# polarshield_v1_4a.net
KiCad netlist of a schematic drawn in EAGLE
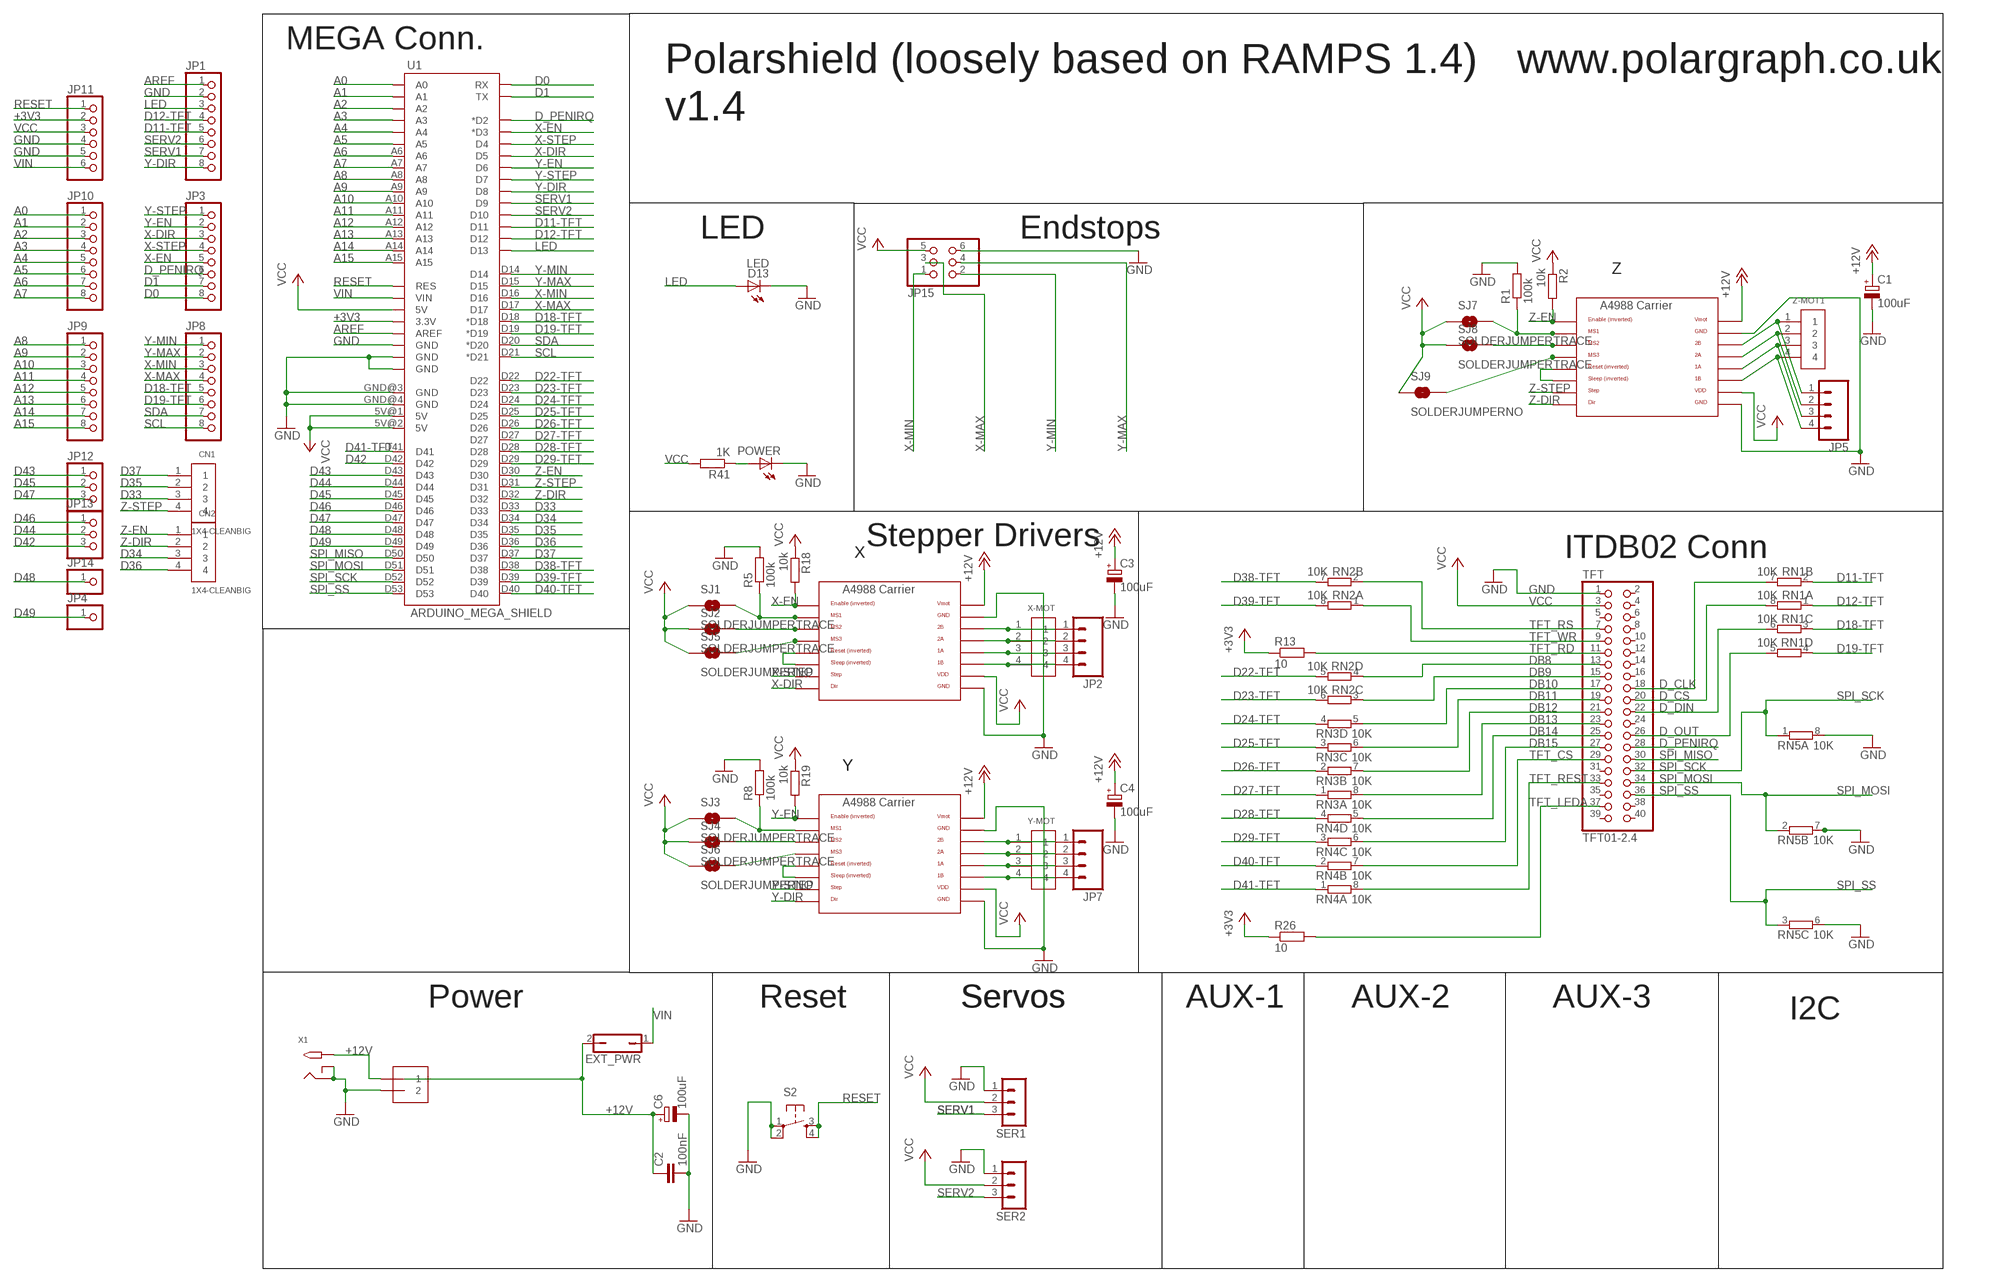
[diagram p0: schematic, sheet 1]

(export (version "E")
  (design (tool "Eeschema 10.0.6"))
  (components
    (comp (ref "C1")
      (value "100uF")
      (footprint "eagle-import:153CLV-0605")
      (libsource (lib "eagle-import") (part "CPOL-EU153CLV-0605"))
    )
    (comp (ref "C2")
      (value "100nF")
      (footprint "eagle-import:C0805")
      (libsource (lib "eagle-import") (part "C-EUC0805"))
    )
    (comp (ref "C3")
      (value "100uF")
      (footprint "eagle-import:153CLV-0605")
      (libsource (lib "eagle-import") (part "CPOL-EU153CLV-0605"))
    )
    (comp (ref "C4")
      (value "100uF")
      (footprint "eagle-import:153CLV-0605")
      (libsource (lib "eagle-import") (part "CPOL-EU153CLV-0605"))
    )
    (comp (ref "C6")
      (value "100uF")
      (footprint "eagle-import:153CLV-0605")
      (libsource (lib "eagle-import") (part "CPOL-EU153CLV-0605"))
    )
    (comp (ref "CN1")
      (value "1X4-CLEANBIG")
      (footprint "eagle-import:1X04-CLEANBIG")
      (libsource (lib "eagle-import") (part "1X4-CLEANBIG"))
    )
    (comp (ref "CN2")
      (value "1X4-CLEANBIG")
      (footprint "eagle-import:1X04-CLEANBIG")
      (libsource (lib "eagle-import") (part "1X4-CLEANBIG"))
    )
    (comp (ref "D13")
      (value "LED")
      (footprint "eagle-import:CHIP-LED0805")
      (libsource (lib "eagle-import") (part "LEDCHIP-LED0805"))
    )
    (comp (ref "EXT_PWR")
      (value "JP1Q")
      (footprint "eagle-import:JP1")
      (libsource (lib "eagle-import") (part "JP1Q"))
    )
    (comp (ref "J1")
      (value "1X2-3.5MM")
      (footprint "eagle-import:1X2-3.5MM")
      (libsource (lib "eagle-import") (part "1X2-3.5MM"))
    )
    (comp (ref "JP1")
      (value "PINHD-1X8CLEANBIG")
      (footprint "eagle-import:1X08-CLEANBIG")
      (libsource (lib "eagle-import") (part "PINHD-1X8CLEANBIG"))
    )
    (comp (ref "JP2")
      (value "M04SCREW")
      (footprint "eagle-import:SCREWTERMINAL-3.5MM-4")
      (libsource (lib "eagle-import") (part "M04SCREW"))
    )
    (comp (ref "JP3")
      (value "PINHD-1X8CLEANBIG")
      (footprint "eagle-import:1X08-CLEANBIG")
      (libsource (lib "eagle-import") (part "PINHD-1X8CLEANBIG"))
    )
    (comp (ref "JP4")
      (value "PINHD-1X1CB")
      (footprint "eagle-import:1X01-CLEANBIG")
      (libsource (lib "eagle-import") (part "PINHD-1X1CB"))
    )
    (comp (ref "JP5")
      (value "M04SCREW")
      (footprint "eagle-import:SCREWTERMINAL-3.5MM-4")
      (libsource (lib "eagle-import") (part "M04SCREW"))
    )
    (comp (ref "JP7")
      (value "M04SCREW")
      (footprint "eagle-import:SCREWTERMINAL-3.5MM-4")
      (libsource (lib "eagle-import") (part "M04SCREW"))
    )
    (comp (ref "JP8")
      (value "PINHD-1X8CLEANBIG")
      (footprint "eagle-import:1X08-CLEANBIG")
      (libsource (lib "eagle-import") (part "PINHD-1X8CLEANBIG"))
    )
    (comp (ref "JP9")
      (value "PINHD-1X8CLEANBIG")
      (footprint "eagle-import:1X08-CLEANBIG")
      (libsource (lib "eagle-import") (part "PINHD-1X8CLEANBIG"))
    )
    (comp (ref "JP10")
      (value "PINHD-1X8CLEANBIG")
      (footprint "eagle-import:1X08-CLEANBIG")
      (libsource (lib "eagle-import") (part "PINHD-1X8CLEANBIG"))
    )
    (comp (ref "JP11")
      (value "PINHD-1X6CB")
      (footprint "eagle-import:1X06-CLEANBIG")
      (libsource (lib "eagle-import") (part "PINHD-1X6CB"))
    )
    (comp (ref "JP12")
      (value "PINHD-1X3CB")
      (footprint "eagle-import:1X03-CLEANBIG")
      (libsource (lib "eagle-import") (part "PINHD-1X3CB"))
    )
    (comp (ref "JP13")
      (value "PINHD-1X3CB")
      (footprint "eagle-import:1X03-CLEANBIG")
      (libsource (lib "eagle-import") (part "PINHD-1X3CB"))
    )
    (comp (ref "JP14")
      (value "PINHD-1X1CB")
      (footprint "eagle-import:1X01-CLEANBIG")
      (libsource (lib "eagle-import") (part "PINHD-1X1CB"))
    )
    (comp (ref "JP15")
      (value "PINHD-2X3")
      (footprint "eagle-import:2X03")
      (libsource (lib "eagle-import") (part "PINHD-2X3"))
    )
    (comp (ref "POWER")
      (value "LEDCHIP-LED0805")
      (footprint "eagle-import:CHIP-LED0805")
      (libsource (lib "eagle-import") (part "LEDCHIP-LED0805"))
    )
    (comp (ref "R1")
      (value "100k")
      (footprint "eagle-import:R0805")
      (libsource (lib "eagle-import") (part "R-EU_R0805"))
    )
    (comp (ref "R2")
      (value "10k")
      (footprint "eagle-import:R0805")
      (libsource (lib "eagle-import") (part "R-EU_R0805"))
    )
    (comp (ref "R5")
      (value "100k")
      (footprint "eagle-import:R0805")
      (libsource (lib "eagle-import") (part "R-EU_R0805"))
    )
    (comp (ref "R8")
      (value "100k")
      (footprint "eagle-import:R0805")
      (libsource (lib "eagle-import") (part "R-EU_R0805"))
    )
    (comp (ref "R13")
      (value "10")
      (footprint "eagle-import:R0805")
      (libsource (lib "eagle-import") (part "resistor_R-EU_R0805"))
    )
    (comp (ref "R18")
      (value "10k")
      (footprint "eagle-import:R0805")
      (libsource (lib "eagle-import") (part "R-EU_R0805"))
    )
    (comp (ref "R19")
      (value "10k")
      (footprint "eagle-import:R0805")
      (libsource (lib "eagle-import") (part "R-EU_R0805"))
    )
    (comp (ref "R26")
      (value "10")
      (footprint "eagle-import:R0805")
      (libsource (lib "eagle-import") (part "resistor_R-EU_R0805"))
    )
    (comp (ref "R41")
      (value "1K")
      (footprint "eagle-import:R0805")
      (libsource (lib "eagle-import") (part "R-EU_R0805"))
    )
    (comp (ref "RN1")
      (value "10K")
      (footprint "eagle-import:EXBS8V")
      (libsource (lib "eagle-import") (part "4R-NEXBS8V"))
    )
    (comp (ref "RN2")
      (value "10K")
      (footprint "eagle-import:EXBS8V")
      (libsource (lib "eagle-import") (part "4R-NEXBS8V"))
    )
    (comp (ref "RN3")
      (value "10K")
      (footprint "eagle-import:EXBS8V")
      (libsource (lib "eagle-import") (part "4R-NEXBS8V"))
    )
    (comp (ref "RN4")
      (value "10K")
      (footprint "eagle-import:EXBS8V")
      (libsource (lib "eagle-import") (part "4R-NEXBS8V"))
    )
    (comp (ref "RN5")
      (value "10K")
      (footprint "eagle-import:EXBS8V")
      (libsource (lib "eagle-import") (part "4R-NEXBS8V"))
    )
    (comp (ref "S2")
      (value "TAC_SWITCHPTH")
      (footprint "eagle-import:TACTILE-PTH")
      (libsource (lib "eagle-import") (part "TAC_SWITCHPTH"))
    )
    (comp (ref "SER1")
      (value "3PIN-HEADER")
      (footprint "eagle-import:3PIN-HEADER")
      (libsource (lib "eagle-import") (part "3PIN-HEADER"))
    )
    (comp (ref "SER2")
      (value "3PIN-HEADER")
      (footprint "eagle-import:3PIN-HEADER")
      (libsource (lib "eagle-import") (part "3PIN-HEADER"))
    )
    (comp (ref "SJ1")
      (value "SOLDERJUMPERTRACE")
      (footprint "eagle-import:SJ_2S-TRACE")
      (libsource (lib "eagle-import") (part "SOLDERJUMPERTRACE"))
    )
    (comp (ref "SJ2")
      (value "SOLDERJUMPERTRACE")
      (footprint "eagle-import:SJ_2S-TRACE")
      (libsource (lib "eagle-import") (part "SOLDERJUMPERTRACE"))
    )
    (comp (ref "SJ3")
      (value "SOLDERJUMPERTRACE")
      (footprint "eagle-import:SJ_2S-TRACE")
      (libsource (lib "eagle-import") (part "SOLDERJUMPERTRACE"))
    )
    (comp (ref "SJ4")
      (value "SOLDERJUMPERTRACE")
      (footprint "eagle-import:SJ_2S-TRACE")
      (libsource (lib "eagle-import") (part "SOLDERJUMPERTRACE"))
    )
    (comp (ref "SJ5")
      (value "SOLDERJUMPERNO")
      (footprint "eagle-import:SJ_2S-NO")
      (libsource (lib "eagle-import") (part "SOLDERJUMPERNO"))
    )
    (comp (ref "SJ6")
      (value "SOLDERJUMPERNO")
      (footprint "eagle-import:SJ_2S-NO")
      (libsource (lib "eagle-import") (part "SOLDERJUMPERNO"))
    )
    (comp (ref "SJ7")
      (value "SOLDERJUMPERTRACE")
      (footprint "eagle-import:SJ_2S-TRACE")
      (libsource (lib "eagle-import") (part "SOLDERJUMPERTRACE"))
    )
    (comp (ref "SJ8")
      (value "SOLDERJUMPERTRACE")
      (footprint "eagle-import:SJ_2S-TRACE")
      (libsource (lib "eagle-import") (part "SOLDERJUMPERTRACE"))
    )
    (comp (ref "SJ9")
      (value "SOLDERJUMPERNO")
      (footprint "eagle-import:SJ_2S-NO")
      (libsource (lib "eagle-import") (part "SOLDERJUMPERNO"))
    )
    (comp (ref "TFT")
      (value "TFT01-2.4")
      (footprint "eagle-import:TFT01-2.4")
      (libsource (lib "eagle-import") (part "TFT01-2.4"))
    )
    (comp (ref "U$1")
      (value "A4988BREAKOUT")
      (footprint "eagle-import:A4988BREAKOUT")
      (libsource (lib "eagle-import") (part "A4988BREAKOUT"))
    )
    (comp (ref "U$6")
      (value "A4988BREAKOUT")
      (footprint "eagle-import:A4988BREAKOUT")
      (libsource (lib "eagle-import") (part "A4988BREAKOUT"))
    )
    (comp (ref "U$7")
      (value "A4988BREAKOUT")
      (footprint "eagle-import:A4988BREAKOUT")
      (libsource (lib "eagle-import") (part "A4988BREAKOUT"))
    )
    (comp (ref "U1")
      (value "ARDUINO_MEGA_SHIELD")
      (footprint "eagle-import:ARDUINO_MEGA_SHIELD")
      (libsource (lib "eagle-import") (part "ARDUINO_MEGA_SHIELD"))
    )
    (comp (ref "X-MOT")
      (value "1X4-BIG")
      (footprint "eagle-import:1X04-BIG")
      (libsource (lib "eagle-import") (part "1X4-BIG"))
    )
    (comp (ref "X1")
      (value "2.1MMJACKTHM")
      (footprint "eagle-import:PJ-102A")
      (libsource (lib "eagle-import") (part "2.1MMJACKTHM"))
    )
    (comp (ref "Y-MOT")
      (value "1X4-BIG")
      (footprint "eagle-import:1X04-BIG")
      (libsource (lib "eagle-import") (part "1X4-BIG"))
    )
    (comp (ref "Z-MOT1")
      (value "1X4-BIG")
      (footprint "eagle-import:1X04-BIG")
      (libsource (lib "eagle-import") (part "1X4-BIG"))
    )
  )
  (nets
    (net (code "1") (name "+3V3") (class "Default")
      (node (ref "JP11") (pin "2") (pinfunction "2_2") (pintype "passive"))
      (node (ref "R13") (pin "1") (pinfunction "1_1") (pintype "passive"))
      (node (ref "R26") (pin "1") (pinfunction "1_1") (pintype "passive"))
      (node (ref "U1") (pin "3.3V") (pinfunction "3.3V_3.3V") (pintype "bidirectional"))
    )
    (net (code "2") (name "+12V") (class "Default")
      (node (ref "C1") (pin "+") (pinfunction "+_+") (pintype "passive"))
      (node (ref "C2") (pin "1") (pinfunction "1_1") (pintype "passive"))
      (node (ref "C3") (pin "+") (pinfunction "+_+") (pintype "passive"))
      (node (ref "C4") (pin "+") (pinfunction "+_+") (pintype "passive"))
      (node (ref "C6") (pin "+") (pinfunction "+_+") (pintype "passive"))
      (node (ref "EXT_PWR") (pin "2") (pinfunction "2_2") (pintype "passive"))
      (node (ref "J1") (pin "1") (pinfunction "1_1") (pintype "passive"))
      (node (ref "U$1") (pin "VMOT") (pinfunction "VMOT_VMOT") (pintype "power_in"))
      (node (ref "U$6") (pin "VMOT") (pinfunction "VMOT_VMOT") (pintype "power_in"))
      (node (ref "U$7") (pin "VMOT") (pinfunction "VMOT_VMOT") (pintype "power_in"))
      (node (ref "X1") (pin "TIP") (pinfunction "TIP_TIP") (pintype "bidirectional"))
    )
    (net (code "3") (name "/A0") (class "Default")
      (node (ref "JP10") (pin "1") (pinfunction "1_1") (pintype "passive"))
      (node (ref "U1") (pin "A0") (pinfunction "A0_A0") (pintype "bidirectional"))
    )
    (net (code "4") (name "/A1") (class "Default")
      (node (ref "JP10") (pin "2") (pinfunction "2_2") (pintype "passive"))
      (node (ref "U1") (pin "A1") (pinfunction "A1_A1") (pintype "bidirectional"))
    )
    (net (code "5") (name "/A2") (class "Default")
      (node (ref "JP10") (pin "3") (pinfunction "3_3") (pintype "passive"))
      (node (ref "U1") (pin "A2") (pinfunction "A2_A2") (pintype "bidirectional"))
    )
    (net (code "6") (name "/A3") (class "Default")
      (node (ref "JP10") (pin "4") (pinfunction "4_4") (pintype "passive"))
      (node (ref "U1") (pin "A3") (pinfunction "A3_A3") (pintype "bidirectional"))
    )
    (net (code "7") (name "/A4") (class "Default")
      (node (ref "JP10") (pin "5") (pinfunction "5_5") (pintype "passive"))
      (node (ref "U1") (pin "A4") (pinfunction "A4_A4") (pintype "bidirectional"))
    )
    (net (code "8") (name "/A5") (class "Default")
      (node (ref "JP10") (pin "6") (pinfunction "6_6") (pintype "passive"))
      (node (ref "U1") (pin "A5") (pinfunction "A5_A5") (pintype "bidirectional"))
    )
    (net (code "9") (name "/A6") (class "Default")
      (node (ref "JP10") (pin "7") (pinfunction "7_7") (pintype "passive"))
      (node (ref "U1") (pin "A6") (pinfunction "A6_A6") (pintype "bidirectional"))
    )
    (net (code "10") (name "/A7") (class "Default")
      (node (ref "JP10") (pin "8") (pinfunction "8_8") (pintype "passive"))
      (node (ref "U1") (pin "A7") (pinfunction "A7_A7") (pintype "bidirectional"))
    )
    (net (code "11") (name "/A8") (class "Default")
      (node (ref "JP9") (pin "1") (pinfunction "1_1") (pintype "passive"))
      (node (ref "U1") (pin "A8") (pinfunction "A8_A8") (pintype "bidirectional"))
    )
    (net (code "12") (name "/A9") (class "Default")
      (node (ref "JP9") (pin "2") (pinfunction "2_2") (pintype "passive"))
      (node (ref "U1") (pin "A9") (pinfunction "A9_A9") (pintype "bidirectional"))
    )
    (net (code "13") (name "/A10") (class "Default")
      (node (ref "JP9") (pin "3") (pinfunction "3_3") (pintype "passive"))
      (node (ref "U1") (pin "A10") (pinfunction "A10_A10") (pintype "bidirectional"))
    )
    (net (code "14") (name "/A11") (class "Default")
      (node (ref "JP9") (pin "4") (pinfunction "4_4") (pintype "passive"))
      (node (ref "U1") (pin "A11") (pinfunction "A11_A11") (pintype "bidirectional"))
    )
    (net (code "15") (name "/A12") (class "Default")
      (node (ref "JP9") (pin "5") (pinfunction "5_5") (pintype "passive"))
      (node (ref "U1") (pin "A12") (pinfunction "A12_A12") (pintype "bidirectional"))
    )
    (net (code "16") (name "/A13") (class "Default")
      (node (ref "JP9") (pin "6") (pinfunction "6_6") (pintype "passive"))
      (node (ref "U1") (pin "A13") (pinfunction "A13_A13") (pintype "bidirectional"))
    )
    (net (code "17") (name "/A14") (class "Default")
      (node (ref "JP9") (pin "7") (pinfunction "7_7") (pintype "passive"))
      (node (ref "U1") (pin "A14") (pinfunction "A14_A14") (pintype "bidirectional"))
    )
    (net (code "18") (name "/A15") (class "Default")
      (node (ref "JP9") (pin "8") (pinfunction "8_8") (pintype "passive"))
      (node (ref "U1") (pin "A15") (pinfunction "A15_A15") (pintype "bidirectional"))
    )
    (net (code "19") (name "/AREF") (class "Default")
      (node (ref "JP1") (pin "1") (pinfunction "1_1") (pintype "passive"))
      (node (ref "U1") (pin "AREF") (pinfunction "AREF_AREF") (pintype "bidirectional"))
    )
    (net (code "20") (name "/D0") (class "Default")
      (node (ref "JP3") (pin "8") (pinfunction "8_8") (pintype "passive"))
      (node (ref "U1") (pin "RX") (pinfunction "RX_RX") (pintype "bidirectional"))
    )
    (net (code "21") (name "/D1") (class "Default")
      (node (ref "JP3") (pin "7") (pinfunction "7_7") (pintype "passive"))
      (node (ref "U1") (pin "TX") (pinfunction "TX_TX") (pintype "bidirectional"))
    )
    (net (code "22") (name "/D11-TFT") (class "Default")
      (node (ref "JP1") (pin "5") (pinfunction "5_5") (pintype "passive"))
      (node (ref "RN1") (pin "2") (pinfunction "1_2") (pintype "passive"))
      (node (ref "U1") (pin "D11") (pinfunction "D11_D11") (pintype "bidirectional"))
    )
    (net (code "23") (name "/D12-TFT") (class "Default")
      (node (ref "JP1") (pin "4") (pinfunction "4_4") (pintype "passive"))
      (node (ref "RN1") (pin "1") (pinfunction "1_1") (pintype "passive"))
      (node (ref "U1") (pin "D12") (pinfunction "D12_D12") (pintype "bidirectional"))
    )
    (net (code "24") (name "/D18-TFT") (class "Default")
      (node (ref "JP8") (pin "5") (pinfunction "5_5") (pintype "passive"))
      (node (ref "RN1") (pin "3") (pinfunction "1_3") (pintype "passive"))
      (node (ref "U1") (pin "D18") (pinfunction "*D18_D18") (pintype "bidirectional"))
    )
    (net (code "25") (name "/D19-TFT") (class "Default")
      (node (ref "JP8") (pin "6") (pinfunction "6_6") (pintype "passive"))
      (node (ref "RN1") (pin "4") (pinfunction "1_4") (pintype "passive"))
      (node (ref "U1") (pin "D19") (pinfunction "*D19_D19") (pintype "bidirectional"))
    )
    (net (code "26") (name "/D22-TFT") (class "Default")
      (node (ref "RN2") (pin "5") (pinfunction "2_5") (pintype "passive"))
      (node (ref "U1") (pin "D22") (pinfunction "D22_D22") (pintype "bidirectional"))
    )
    (net (code "27") (name "/D23-TFT") (class "Default")
      (node (ref "RN2") (pin "6") (pinfunction "2_6") (pintype "passive"))
      (node (ref "U1") (pin "D23") (pinfunction "D23_D23") (pintype "bidirectional"))
    )
    (net (code "28") (name "/D24-TFT") (class "Default")
      (node (ref "RN3") (pin "4") (pinfunction "1_4") (pintype "passive"))
      (node (ref "U1") (pin "D24") (pinfunction "D24_D24") (pintype "bidirectional"))
    )
    (net (code "29") (name "/D25-TFT") (class "Default")
      (node (ref "RN3") (pin "3") (pinfunction "1_3") (pintype "passive"))
      (node (ref "U1") (pin "D25") (pinfunction "D25_D25") (pintype "bidirectional"))
    )
    (net (code "30") (name "/D26-TFT") (class "Default")
      (node (ref "RN3") (pin "2") (pinfunction "1_2") (pintype "passive"))
      (node (ref "U1") (pin "D26") (pinfunction "D26_D26") (pintype "bidirectional"))
    )
    (net (code "31") (name "/D27-TFT") (class "Default")
      (node (ref "RN3") (pin "1") (pinfunction "1_1") (pintype "passive"))
      (node (ref "U1") (pin "D27") (pinfunction "D27_D27") (pintype "bidirectional"))
    )
    (net (code "32") (name "/D28-TFT") (class "Default")
      (node (ref "RN4") (pin "4") (pinfunction "1_4") (pintype "passive"))
      (node (ref "U1") (pin "D28") (pinfunction "D28_D28") (pintype "bidirectional"))
    )
    (net (code "33") (name "/D29-TFT") (class "Default")
      (node (ref "RN4") (pin "3") (pinfunction "1_3") (pintype "passive"))
      (node (ref "U1") (pin "D29") (pinfunction "D29_D29") (pintype "bidirectional"))
    )
    (net (code "34") (name "/D33") (class "Default")
      (node (ref "CN1") (pin "3") (pinfunction "3_3") (pintype "bidirectional"))
      (node (ref "U1") (pin "D33") (pinfunction "D33_D33") (pintype "bidirectional"))
    )
    (net (code "35") (name "/D34") (class "Default")
      (node (ref "CN2") (pin "3") (pinfunction "3_3") (pintype "bidirectional"))
      (node (ref "U1") (pin "D34") (pinfunction "D34_D34") (pintype "bidirectional"))
    )
    (net (code "36") (name "/D35") (class "Default")
      (node (ref "CN1") (pin "2") (pinfunction "2_2") (pintype "bidirectional"))
      (node (ref "U1") (pin "D35") (pinfunction "D35_D35") (pintype "bidirectional"))
    )
    (net (code "37") (name "/D36") (class "Default")
      (node (ref "CN2") (pin "4") (pinfunction "4_4") (pintype "bidirectional"))
      (node (ref "U1") (pin "D36") (pinfunction "D36_D36") (pintype "bidirectional"))
    )
    (net (code "38") (name "/D37") (class "Default")
      (node (ref "CN1") (pin "1") (pinfunction "1_1") (pintype "bidirectional"))
      (node (ref "U1") (pin "D37") (pinfunction "D37_D37") (pintype "bidirectional"))
    )
    (net (code "39") (name "/D38-TFT") (class "Default")
      (node (ref "RN2") (pin "7") (pinfunction "2_7") (pintype "passive"))
      (node (ref "U1") (pin "D38") (pinfunction "D38_D38") (pintype "bidirectional"))
    )
    (net (code "40") (name "/D39-TFT") (class "Default")
      (node (ref "RN2") (pin "8") (pinfunction "2_8") (pintype "passive"))
      (node (ref "U1") (pin "D39") (pinfunction "D39_D39") (pintype "bidirectional"))
    )
    (net (code "41") (name "/D40-TFT") (class "Default")
      (node (ref "RN4") (pin "2") (pinfunction "1_2") (pintype "passive"))
      (node (ref "U1") (pin "D40") (pinfunction "D40_D40") (pintype "bidirectional"))
    )
    (net (code "42") (name "/D41-TFT") (class "Default")
      (node (ref "RN4") (pin "1") (pinfunction "1_1") (pintype "passive"))
      (node (ref "U1") (pin "D41") (pinfunction "D41_D41") (pintype "bidirectional"))
    )
    (net (code "43") (name "/D42") (class "Default")
      (node (ref "JP13") (pin "3") (pinfunction "3_3") (pintype "passive"))
      (node (ref "U1") (pin "D42") (pinfunction "D42_D42") (pintype "bidirectional"))
    )
    (net (code "44") (name "/D43") (class "Default")
      (node (ref "JP12") (pin "1") (pinfunction "1_1") (pintype "passive"))
      (node (ref "U1") (pin "D43") (pinfunction "D43_D43") (pintype "bidirectional"))
    )
    (net (code "45") (name "/D44") (class "Default")
      (node (ref "JP13") (pin "2") (pinfunction "2_2") (pintype "passive"))
      (node (ref "U1") (pin "D44") (pinfunction "D44_D44") (pintype "bidirectional"))
    )
    (net (code "46") (name "/D45") (class "Default")
      (node (ref "JP12") (pin "2") (pinfunction "2_2") (pintype "passive"))
      (node (ref "U1") (pin "D45") (pinfunction "D45_D45") (pintype "bidirectional"))
    )
    (net (code "47") (name "/D46") (class "Default")
      (node (ref "JP13") (pin "1") (pinfunction "1_1") (pintype "passive"))
      (node (ref "U1") (pin "D46") (pinfunction "D46_D46") (pintype "bidirectional"))
    )
    (net (code "48") (name "/D47") (class "Default")
      (node (ref "JP12") (pin "3") (pinfunction "3_3") (pintype "passive"))
      (node (ref "U1") (pin "D47") (pinfunction "D47_D47") (pintype "bidirectional"))
    )
    (net (code "49") (name "/D48") (class "Default")
      (node (ref "JP14") (pin "1") (pinfunction "1_1") (pintype "passive"))
      (node (ref "U1") (pin "D48") (pinfunction "D48_D48") (pintype "bidirectional"))
    )
    (net (code "50") (name "/D49") (class "Default")
      (node (ref "JP4") (pin "1") (pinfunction "1_1") (pintype "passive"))
      (node (ref "U1") (pin "D49") (pinfunction "D49_D49") (pintype "bidirectional"))
    )
    (net (code "51") (name "/DB8") (class "Default")
      (node (ref "RN2") (pin "4") (pinfunction "1_4") (pintype "passive"))
      (node (ref "TFT") (pin "13") (pinfunction "13_13") (pintype "passive"))
    )
    (net (code "52") (name "/DB9") (class "Default")
      (node (ref "RN2") (pin "3") (pinfunction "1_3") (pintype "passive"))
      (node (ref "TFT") (pin "15") (pinfunction "15_15") (pintype "passive"))
    )
    (net (code "53") (name "/DB10") (class "Default")
      (node (ref "RN3") (pin "5") (pinfunction "2_5") (pintype "passive"))
      (node (ref "TFT") (pin "17") (pinfunction "17_17") (pintype "passive"))
    )
    (net (code "54") (name "/DB11") (class "Default")
      (node (ref "RN3") (pin "6") (pinfunction "2_6") (pintype "passive"))
      (node (ref "TFT") (pin "19") (pinfunction "19_19") (pintype "passive"))
    )
    (net (code "55") (name "/DB12") (class "Default")
      (node (ref "RN3") (pin "7") (pinfunction "2_7") (pintype "passive"))
      (node (ref "TFT") (pin "21") (pinfunction "21_21") (pintype "passive"))
    )
    (net (code "56") (name "/DB13") (class "Default")
      (node (ref "RN3") (pin "8") (pinfunction "2_8") (pintype "passive"))
      (node (ref "TFT") (pin "23") (pinfunction "23_23") (pintype "passive"))
    )
    (net (code "57") (name "/DB14") (class "Default")
      (node (ref "RN4") (pin "5") (pinfunction "2_5") (pintype "passive"))
      (node (ref "TFT") (pin "25") (pinfunction "25_25") (pintype "passive"))
    )
    (net (code "58") (name "/DB15") (class "Default")
      (node (ref "RN4") (pin "6") (pinfunction "2_6") (pintype "passive"))
      (node (ref "TFT") (pin "27") (pinfunction "27_27") (pintype "passive"))
    )
    (net (code "59") (name "/D_CLK") (class "Default")
      (node (ref "RN1") (pin "7") (pinfunction "2_7") (pintype "passive"))
      (node (ref "TFT") (pin "18") (pinfunction "18_18") (pintype "passive"))
    )
    (net (code "60") (name "/D_CS") (class "Default")
      (node (ref "RN1") (pin "8") (pinfunction "2_8") (pintype "passive"))
      (node (ref "TFT") (pin "20") (pinfunction "20_20") (pintype "passive"))
    )
    (net (code "61") (name "/D_DIN") (class "Default")
      (node (ref "RN1") (pin "6") (pinfunction "2_6") (pintype "passive"))
      (node (ref "TFT") (pin "22") (pinfunction "22_22") (pintype "passive"))
    )
    (net (code "62") (name "/D_OUT") (class "Default")
      (node (ref "RN1") (pin "5") (pinfunction "2_5") (pintype "passive"))
      (node (ref "TFT") (pin "26") (pinfunction "26_26") (pintype "passive"))
    )
    (net (code "63") (name "/D_PENIRQ") (class "Default")
      (node (ref "JP3") (pin "6") (pinfunction "6_6") (pintype "passive"))
      (node (ref "TFT") (pin "28") (pinfunction "28_28") (pintype "passive"))
      (node (ref "U1") (pin "D2") (pinfunction "*D2_D2") (pintype "bidirectional"))
    )
    (net (code "64") (name "/LED") (class "Default")
      (node (ref "D13") (pin "A") (pinfunction "A_A") (pintype "passive"))
      (node (ref "JP1") (pin "3") (pinfunction "3_3") (pintype "passive"))
      (node (ref "U1") (pin "D13") (pinfunction "D13_D13") (pintype "bidirectional"))
    )
    (net (code "65") (name "/RESET") (class "Default")
      (node (ref "JP11") (pin "1") (pinfunction "1_1") (pintype "passive"))
      (node (ref "S2") (pin "3") (pinfunction "3_3") (pintype "passive"))
      (node (ref "S2") (pin "4") (pinfunction "4_4") (pintype "passive"))
      (node (ref "U1") (pin "RES") (pinfunction "RES_RES") (pintype "bidirectional"))
    )
    (net (code "66") (name "/SCL") (class "Default")
      (node (ref "JP8") (pin "8") (pinfunction "8_8") (pintype "passive"))
      (node (ref "U1") (pin "D21") (pinfunction "*D21_D21") (pintype "bidirectional"))
    )
    (net (code "67") (name "/SDA") (class "Default")
      (node (ref "JP8") (pin "7") (pinfunction "7_7") (pintype "passive"))
      (node (ref "U1") (pin "D20") (pinfunction "*D20_D20") (pintype "bidirectional"))
    )
    (net (code "68") (name "/SERV1") (class "Default")
      (node (ref "JP1") (pin "7") (pinfunction "7_7") (pintype "passive"))
      (node (ref "SER1") (pin "3") (pinfunction "3_3") (pintype "passive"))
      (node (ref "U1") (pin "D9") (pinfunction "D9_D9") (pintype "bidirectional"))
    )
    (net (code "69") (name "/SERV2") (class "Default")
      (node (ref "JP1") (pin "6") (pinfunction "6_6") (pintype "passive"))
      (node (ref "SER2") (pin "3") (pinfunction "3_3") (pintype "passive"))
      (node (ref "U1") (pin "D10") (pinfunction "D10_D10") (pintype "bidirectional"))
    )
    (net (code "70") (name "/SPI_MISO") (class "Default")
      (node (ref "TFT") (pin "30") (pinfunction "30_30") (pintype "passive"))
      (node (ref "U1") (pin "D50") (pinfunction "D50_D50") (pintype "bidirectional"))
    )
    (net (code "71") (name "/SPI_MOSI") (class "Default")
      (node (ref "RN5") (pin "2") (pinfunction "1_2") (pintype "passive"))
      (node (ref "TFT") (pin "34") (pinfunction "34_34") (pintype "passive"))
      (node (ref "U1") (pin "D51") (pinfunction "D51_D51") (pintype "bidirectional"))
    )
    (net (code "72") (name "/SPI_SCK") (class "Default")
      (node (ref "RN5") (pin "1") (pinfunction "1_1") (pintype "passive"))
      (node (ref "TFT") (pin "32") (pinfunction "32_32") (pintype "passive"))
      (node (ref "U1") (pin "D52") (pinfunction "D52_D52") (pintype "bidirectional"))
    )
    (net (code "73") (name "/SPI_SS") (class "Default")
      (node (ref "RN5") (pin "3") (pinfunction "1_3") (pintype "passive"))
      (node (ref "TFT") (pin "36") (pinfunction "36_36") (pintype "passive"))
      (node (ref "U1") (pin "D53") (pinfunction "D53_D53") (pintype "bidirectional"))
    )
    (net (code "74") (name "/TFT_CS") (class "Default")
      (node (ref "RN4") (pin "7") (pinfunction "2_7") (pintype "passive"))
      (node (ref "TFT") (pin "29") (pinfunction "29_29") (pintype "passive"))
    )
    (net (code "75") (name "/TFT_LEDA") (class "Default")
      (node (ref "R26") (pin "2") (pinfunction "2_2") (pintype "passive"))
      (node (ref "TFT") (pin "37") (pinfunction "37_37") (pintype "passive"))
    )
    (net (code "76") (name "/TFT_RD") (class "Default")
      (node (ref "R13") (pin "2") (pinfunction "2_2") (pintype "passive"))
      (node (ref "TFT") (pin "11") (pinfunction "11_11") (pintype "passive"))
    )
    (net (code "77") (name "/TFT_REST") (class "Default")
      (node (ref "RN4") (pin "8") (pinfunction "2_8") (pintype "passive"))
      (node (ref "TFT") (pin "33") (pinfunction "33_33") (pintype "passive"))
    )
    (net (code "78") (name "/TFT_RS") (class "Default")
      (node (ref "RN2") (pin "2") (pinfunction "1_2") (pintype "passive"))
      (node (ref "TFT") (pin "7") (pinfunction "7_7") (pintype "passive"))
    )
    (net (code "79") (name "/TFT_WR") (class "Default")
      (node (ref "RN2") (pin "1") (pinfunction "1_1") (pintype "passive"))
      (node (ref "TFT") (pin "9") (pinfunction "9_9") (pintype "passive"))
    )
    (net (code "80") (name "/VIN") (class "Default")
      (node (ref "EXT_PWR") (pin "1") (pinfunction "1_1") (pintype "passive"))
      (node (ref "JP11") (pin "6") (pinfunction "6_6") (pintype "passive"))
      (node (ref "U1") (pin "VIN") (pinfunction "VIN_VIN") (pintype "bidirectional"))
    )
    (net (code "81") (name "/X-DIR") (class "Default")
      (node (ref "JP3") (pin "3") (pinfunction "3_3") (pintype "passive"))
      (node (ref "U$6") (pin "DIR") (pinfunction "DIR_DIR") (pintype "input"))
      (node (ref "U1") (pin "D5") (pinfunction "D5_D5") (pintype "bidirectional"))
    )
    (net (code "82") (name "/X-EN") (class "Default")
      (node (ref "JP3") (pin "5") (pinfunction "5_5") (pintype "passive"))
      (node (ref "R18") (pin "2") (pinfunction "2_2") (pintype "passive"))
      (node (ref "U$6") (pin "EN") (pinfunction "EN_EN") (pintype "input"))
      (node (ref "U1") (pin "D3") (pinfunction "*D3_D3") (pintype "bidirectional"))
    )
    (net (code "83") (name "/X-MAX") (class "Default")
      (node (ref "JP15") (pin "3") (pinfunction "3_3") (pintype "passive"))
      (node (ref "JP8") (pin "4") (pinfunction "4_4") (pintype "passive"))
      (node (ref "U1") (pin "D17") (pinfunction "D17_D17") (pintype "bidirectional"))
    )
    (net (code "84") (name "/X-MIN") (class "Default")
      (node (ref "JP15") (pin "1") (pinfunction "1_1") (pintype "passive"))
      (node (ref "JP8") (pin "3") (pinfunction "3_3") (pintype "passive"))
      (node (ref "U1") (pin "D16") (pinfunction "D16_D16") (pintype "bidirectional"))
    )
    (net (code "85") (name "/X-STEP") (class "Default")
      (node (ref "JP3") (pin "4") (pinfunction "4_4") (pintype "passive"))
      (node (ref "U$6") (pin "STEP") (pinfunction "STEP_STEP") (pintype "input"))
      (node (ref "U1") (pin "D4") (pinfunction "D4_D4") (pintype "bidirectional"))
    )
    (net (code "86") (name "/Y-DIR") (class "Default")
      (node (ref "JP1") (pin "8") (pinfunction "8_8") (pintype "passive"))
      (node (ref "U$7") (pin "DIR") (pinfunction "DIR_DIR") (pintype "input"))
      (node (ref "U1") (pin "D8") (pinfunction "D8_D8") (pintype "bidirectional"))
    )
    (net (code "87") (name "/Y-EN") (class "Default")
      (node (ref "JP3") (pin "2") (pinfunction "2_2") (pintype "passive"))
      (node (ref "R19") (pin "2") (pinfunction "2_2") (pintype "passive"))
      (node (ref "U$7") (pin "EN") (pinfunction "EN_EN") (pintype "input"))
      (node (ref "U1") (pin "D6") (pinfunction "D6_D6") (pintype "bidirectional"))
    )
    (net (code "88") (name "/Y-MAX") (class "Default")
      (node (ref "JP15") (pin "4") (pinfunction "4_4") (pintype "passive"))
      (node (ref "JP8") (pin "2") (pinfunction "2_2") (pintype "passive"))
      (node (ref "U1") (pin "D15") (pinfunction "D15_D15") (pintype "bidirectional"))
    )
    (net (code "89") (name "/Y-MIN") (class "Default")
      (node (ref "JP15") (pin "2") (pinfunction "2_2") (pintype "passive"))
      (node (ref "JP8") (pin "1") (pinfunction "1_1") (pintype "passive"))
      (node (ref "U1") (pin "D14") (pinfunction "D14_D14") (pintype "bidirectional"))
    )
    (net (code "90") (name "/Y-STEP") (class "Default")
      (node (ref "JP3") (pin "1") (pinfunction "1_1") (pintype "passive"))
      (node (ref "U$7") (pin "STEP") (pinfunction "STEP_STEP") (pintype "input"))
      (node (ref "U1") (pin "D7") (pinfunction "D7_D7") (pintype "bidirectional"))
    )
    (net (code "91") (name "/Z-DIR") (class "Default")
      (node (ref "CN2") (pin "2") (pinfunction "2_2") (pintype "bidirectional"))
      (node (ref "U$1") (pin "DIR") (pinfunction "DIR_DIR") (pintype "input"))
      (node (ref "U1") (pin "D32") (pinfunction "D32_D32") (pintype "bidirectional"))
    )
    (net (code "92") (name "/Z-EN") (class "Default")
      (node (ref "CN2") (pin "1") (pinfunction "1_1") (pintype "bidirectional"))
      (node (ref "R2") (pin "2") (pinfunction "2_2") (pintype "passive"))
      (node (ref "U$1") (pin "EN") (pinfunction "EN_EN") (pintype "input"))
      (node (ref "U1") (pin "D30") (pinfunction "D30_D30") (pintype "bidirectional"))
    )
    (net (code "93") (name "/Z-STEP") (class "Default")
      (node (ref "CN1") (pin "4") (pinfunction "4_4") (pintype "bidirectional"))
      (node (ref "U$1") (pin "STEP") (pinfunction "STEP_STEP") (pintype "input"))
      (node (ref "U1") (pin "D31") (pinfunction "D31_D31") (pintype "bidirectional"))
    )
    (net (code "94") (name "GND") (class "Default")
      (node (ref "C1") (pin "-") (pinfunction "-_-") (pintype "passive"))
      (node (ref "C2") (pin "2") (pinfunction "2_2") (pintype "passive"))
      (node (ref "C3") (pin "-") (pinfunction "-_-") (pintype "passive"))
      (node (ref "C4") (pin "-") (pinfunction "-_-") (pintype "passive"))
      (node (ref "C6") (pin "-") (pinfunction "-_-") (pintype "passive"))
      (node (ref "D13") (pin "C") (pinfunction "C_C") (pintype "passive"))
      (node (ref "J1") (pin "2") (pinfunction "2_2") (pintype "passive"))
      (node (ref "JP1") (pin "2") (pinfunction "2_2") (pintype "passive"))
      (node (ref "JP11") (pin "4") (pinfunction "4_4") (pintype "passive"))
      (node (ref "JP11") (pin "5") (pinfunction "5_5") (pintype "passive"))
      (node (ref "JP15") (pin "6") (pinfunction "6_6") (pintype "passive"))
      (node (ref "POWER") (pin "C") (pinfunction "C_C") (pintype "passive"))
      (node (ref "R1") (pin "2") (pinfunction "2_2") (pintype "passive"))
      (node (ref "R5") (pin "2") (pinfunction "2_2") (pintype "passive"))
      (node (ref "R8") (pin "2") (pinfunction "2_2") (pintype "passive"))
      (node (ref "RN5") (pin "6") (pinfunction "2_6") (pintype "passive"))
      (node (ref "RN5") (pin "7") (pinfunction "2_7") (pintype "passive"))
      (node (ref "RN5") (pin "8") (pinfunction "2_8") (pintype "passive"))
      (node (ref "S2") (pin "1") (pinfunction "1_1") (pintype "passive"))
      (node (ref "S2") (pin "2") (pinfunction "2_2") (pintype "passive"))
      (node (ref "SER1") (pin "1") (pinfunction "1_1") (pintype "passive"))
      (node (ref "SER2") (pin "1") (pinfunction "1_1") (pintype "passive"))
      (node (ref "TFT") (pin "1") (pinfunction "1_1") (pintype "passive"))
      (node (ref "U$1") (pin "GND") (pinfunction "GND_GND") (pintype "power_in"))
      (node (ref "U$1") (pin "GND@0") (pinfunction "GND_GND@0") (pintype "power_in"))
      (node (ref "U$6") (pin "GND") (pinfunction "GND_GND") (pintype "power_in"))
      (node (ref "U$6") (pin "GND@0") (pinfunction "GND_GND@0") (pintype "power_in"))
      (node (ref "U$7") (pin "GND") (pinfunction "GND_GND") (pintype "power_in"))
      (node (ref "U$7") (pin "GND@0") (pinfunction "GND_GND@0") (pintype "power_in"))
      (node (ref "U1") (pin "GND@0") (pinfunction "GND_GND@0") (pintype "power_in"))
      (node (ref "U1") (pin "GND@1") (pinfunction "GND_GND@1") (pintype "power_in"))
      (node (ref "U1") (pin "GND@2") (pinfunction "GND_GND@2") (pintype "power_in"))
      (node (ref "U1") (pin "GND@3") (pinfunction "GND_GND@3") (pintype "power_in"))
      (node (ref "U1") (pin "GND@4") (pinfunction "GND_GND@4") (pintype "power_in"))
      (node (ref "X1") (pin "RING") (pinfunction "RING_RING") (pintype "bidirectional"))
      (node (ref "X1") (pin "RING_SW") (pinfunction "RING_SW_RING_SW") (pintype "bidirectional"))
    )
    (net (code "95") (name "Net-(JP2-Pad1)") (class "Default")
      (node (ref "JP2") (pin "1") (pinfunction "1_1") (pintype "passive"))
      (node (ref "U$6") (pin "2B") (pinfunction "2B_2B") (pintype "output"))
      (node (ref "X-MOT") (pin "1") (pinfunction "1_1") (pintype "bidirectional"))
    )
    (net (code "96") (name "Net-(JP2-Pad2)") (class "Default")
      (node (ref "JP2") (pin "2") (pinfunction "2_2") (pintype "passive"))
      (node (ref "U$6") (pin "2A") (pinfunction "2A_2A") (pintype "output"))
      (node (ref "X-MOT") (pin "2") (pinfunction "2_2") (pintype "bidirectional"))
    )
    (net (code "97") (name "Net-(JP2-Pad3)") (class "Default")
      (node (ref "JP2") (pin "3") (pinfunction "3_3") (pintype "passive"))
      (node (ref "U$6") (pin "1A") (pinfunction "1A_1A") (pintype "output"))
      (node (ref "X-MOT") (pin "3") (pinfunction "3_3") (pintype "bidirectional"))
    )
    (net (code "98") (name "Net-(JP2-Pad4)") (class "Default")
      (node (ref "JP2") (pin "4") (pinfunction "4_4") (pintype "passive"))
      (node (ref "U$6") (pin "1B") (pinfunction "1B_1B") (pintype "output"))
      (node (ref "X-MOT") (pin "4") (pinfunction "4_4") (pintype "bidirectional"))
    )
    (net (code "99") (name "Net-(JP5-Pad1)") (class "Default")
      (node (ref "JP5") (pin "1") (pinfunction "1_1") (pintype "passive"))
      (node (ref "U$1") (pin "2B") (pinfunction "2B_2B") (pintype "output"))
      (node (ref "Z-MOT1") (pin "1") (pinfunction "1_1") (pintype "bidirectional"))
    )
    (net (code "100") (name "Net-(JP5-Pad2)") (class "Default")
      (node (ref "JP5") (pin "2") (pinfunction "2_2") (pintype "passive"))
      (node (ref "U$1") (pin "2A") (pinfunction "2A_2A") (pintype "output"))
      (node (ref "Z-MOT1") (pin "2") (pinfunction "2_2") (pintype "bidirectional"))
    )
    (net (code "101") (name "Net-(JP5-Pad3)") (class "Default")
      (node (ref "JP5") (pin "3") (pinfunction "3_3") (pintype "passive"))
      (node (ref "U$1") (pin "1A") (pinfunction "1A_1A") (pintype "output"))
      (node (ref "Z-MOT1") (pin "3") (pinfunction "3_3") (pintype "bidirectional"))
    )
    (net (code "102") (name "Net-(JP5-Pad4)") (class "Default")
      (node (ref "JP5") (pin "4") (pinfunction "4_4") (pintype "passive"))
      (node (ref "U$1") (pin "1B") (pinfunction "1B_1B") (pintype "output"))
      (node (ref "Z-MOT1") (pin "4") (pinfunction "4_4") (pintype "bidirectional"))
    )
    (net (code "103") (name "Net-(JP7-Pad1)") (class "Default")
      (node (ref "JP7") (pin "1") (pinfunction "1_1") (pintype "passive"))
      (node (ref "U$7") (pin "2B") (pinfunction "2B_2B") (pintype "output"))
      (node (ref "Y-MOT") (pin "1") (pinfunction "1_1") (pintype "bidirectional"))
    )
    (net (code "104") (name "Net-(JP7-Pad2)") (class "Default")
      (node (ref "JP7") (pin "2") (pinfunction "2_2") (pintype "passive"))
      (node (ref "U$7") (pin "2A") (pinfunction "2A_2A") (pintype "output"))
      (node (ref "Y-MOT") (pin "2") (pinfunction "2_2") (pintype "bidirectional"))
    )
    (net (code "105") (name "Net-(JP7-Pad3)") (class "Default")
      (node (ref "JP7") (pin "3") (pinfunction "3_3") (pintype "passive"))
      (node (ref "U$7") (pin "1A") (pinfunction "1A_1A") (pintype "output"))
      (node (ref "Y-MOT") (pin "3") (pinfunction "3_3") (pintype "bidirectional"))
    )
    (net (code "106") (name "Net-(JP7-Pad4)") (class "Default")
      (node (ref "JP7") (pin "4") (pinfunction "4_4") (pintype "passive"))
      (node (ref "U$7") (pin "1B") (pinfunction "1B_1B") (pintype "output"))
      (node (ref "Y-MOT") (pin "4") (pinfunction "4_4") (pintype "bidirectional"))
    )
    (net (code "107") (name "Net-(POWER-PadA)") (class "Default")
      (node (ref "POWER") (pin "A") (pinfunction "A_A") (pintype "passive"))
      (node (ref "R41") (pin "1") (pinfunction "1_1") (pintype "passive"))
    )
    (net (code "108") (name "Net-(R1-Pad1)") (class "Default")
      (node (ref "R1") (pin "1") (pinfunction "1_1") (pintype "passive"))
      (node (ref "SJ7") (pin "2") (pinfunction "2_2") (pintype "passive"))
      (node (ref "U$1") (pin "MS1") (pinfunction "MS1_MS1") (pintype "input"))
    )
    (net (code "109") (name "Net-(R5-Pad1)") (class "Default")
      (node (ref "R5") (pin "1") (pinfunction "1_1") (pintype "passive"))
      (node (ref "SJ1") (pin "2") (pinfunction "2_2") (pintype "passive"))
      (node (ref "U$6") (pin "MS1") (pinfunction "MS1_MS1") (pintype "input"))
    )
    (net (code "110") (name "Net-(R8-Pad1)") (class "Default")
      (node (ref "R8") (pin "1") (pinfunction "1_1") (pintype "passive"))
      (node (ref "SJ3") (pin "2") (pinfunction "2_2") (pintype "passive"))
      (node (ref "U$7") (pin "MS1") (pinfunction "MS1_MS1") (pintype "input"))
    )
    (net (code "111") (name "Net-(SJ2-Pad2)") (class "Default")
      (node (ref "SJ2") (pin "2") (pinfunction "2_2") (pintype "passive"))
      (node (ref "U$6") (pin "MS2") (pinfunction "MS2_MS2") (pintype "input"))
    )
    (net (code "112") (name "Net-(SJ4-Pad2)") (class "Default")
      (node (ref "SJ4") (pin "2") (pinfunction "2_2") (pintype "passive"))
      (node (ref "U$7") (pin "MS2") (pinfunction "MS2_MS2") (pintype "input"))
    )
    (net (code "113") (name "Net-(SJ5-Pad2)") (class "Default")
      (node (ref "SJ5") (pin "2") (pinfunction "2_2") (pintype "passive"))
      (node (ref "U$6") (pin "MS3") (pinfunction "MS3_MS3") (pintype "input"))
    )
    (net (code "114") (name "Net-(SJ6-Pad2)") (class "Default")
      (node (ref "SJ6") (pin "2") (pinfunction "2_2") (pintype "passive"))
      (node (ref "U$7") (pin "MS3") (pinfunction "MS3_MS3") (pintype "input"))
    )
    (net (code "115") (name "Net-(SJ8-Pad2)") (class "Default")
      (node (ref "SJ8") (pin "2") (pinfunction "2_2") (pintype "passive"))
      (node (ref "U$1") (pin "MS2") (pinfunction "MS2_MS2") (pintype "input"))
    )
    (net (code "116") (name "Net-(SJ9-Pad2)") (class "Default")
      (node (ref "SJ9") (pin "2") (pinfunction "2_2") (pintype "passive"))
      (node (ref "U$1") (pin "MS3") (pinfunction "MS3_MS3") (pintype "input"))
    )
    (net (code "117") (name "Net-(U$1-SLEEP)") (class "Default")
      (node (ref "U$1") (pin "RST") (pinfunction "RST_RST") (pintype "input"))
      (node (ref "U$1") (pin "SLP") (pinfunction "SLEEP_SLP") (pintype "input"))
    )
    (net (code "118") (name "Net-(U$6-SLEEP)") (class "Default")
      (node (ref "U$6") (pin "RST") (pinfunction "RST_RST") (pintype "input"))
      (node (ref "U$6") (pin "SLP") (pinfunction "SLEEP_SLP") (pintype "input"))
    )
    (net (code "119") (name "Net-(U$7-SLEEP)") (class "Default")
      (node (ref "U$7") (pin "RST") (pinfunction "RST_RST") (pintype "input"))
      (node (ref "U$7") (pin "SLP") (pinfunction "SLEEP_SLP") (pintype "input"))
    )
    (net (code "120") (name "VCC") (class "Default")
      (node (ref "JP11") (pin "3") (pinfunction "3_3") (pintype "passive"))
      (node (ref "JP15") (pin "5") (pinfunction "5_5") (pintype "passive"))
      (node (ref "R18") (pin "1") (pinfunction "1_1") (pintype "passive"))
      (node (ref "R19") (pin "1") (pinfunction "1_1") (pintype "passive"))
      (node (ref "R2") (pin "1") (pinfunction "1_1") (pintype "passive"))
      (node (ref "R41") (pin "2") (pinfunction "2_2") (pintype "passive"))
      (node (ref "SER1") (pin "2") (pinfunction "2_2") (pintype "passive"))
      (node (ref "SER2") (pin "2") (pinfunction "2_2") (pintype "passive"))
      (node (ref "SJ1") (pin "1") (pinfunction "1_1") (pintype "passive"))
      (node (ref "SJ2") (pin "1") (pinfunction "1_1") (pintype "passive"))
      (node (ref "SJ3") (pin "1") (pinfunction "1_1") (pintype "passive"))
      (node (ref "SJ4") (pin "1") (pinfunction "1_1") (pintype "passive"))
      (node (ref "SJ5") (pin "1") (pinfunction "1_1") (pintype "passive"))
      (node (ref "SJ6") (pin "1") (pinfunction "1_1") (pintype "passive"))
      (node (ref "SJ7") (pin "1") (pinfunction "1_1") (pintype "passive"))
      (node (ref "SJ8") (pin "1") (pinfunction "1_1") (pintype "passive"))
      (node (ref "SJ9") (pin "1") (pinfunction "1_1") (pintype "passive"))
      (node (ref "TFT") (pin "3") (pinfunction "3_3") (pintype "passive"))
      (node (ref "U$1") (pin "VDD") (pinfunction "VDD_VDD") (pintype "power_in"))
      (node (ref "U$6") (pin "VDD") (pinfunction "VDD_VDD") (pintype "power_in"))
      (node (ref "U$7") (pin "VDD") (pinfunction "VDD_VDD") (pintype "power_in"))
      (node (ref "U1") (pin "5V@0") (pinfunction "5V_5V@0") (pintype "power_in"))
      (node (ref "U1") (pin "5V@1") (pinfunction "5V_5V@1") (pintype "power_in"))
      (node (ref "U1") (pin "5V@2") (pinfunction "5V_5V@2") (pintype "power_in"))
    )
    (net (code "121") (name "unconnected-(TFT-Pad2)") (class "Default")
      (node (ref "TFT") (pin "2") (pinfunction "2_2") (pintype "passive"))
    )
    (net (code "122") (name "unconnected-(TFT-Pad4)") (class "Default")
      (node (ref "TFT") (pin "4") (pinfunction "4_4") (pintype "passive"))
    )
    (net (code "123") (name "unconnected-(TFT-Pad5)") (class "Default")
      (node (ref "TFT") (pin "5") (pinfunction "5_5") (pintype "passive"))
    )
    (net (code "124") (name "unconnected-(TFT-Pad6)") (class "Default")
      (node (ref "TFT") (pin "6") (pinfunction "6_6") (pintype "passive"))
    )
    (net (code "125") (name "unconnected-(TFT-Pad8)") (class "Default")
      (node (ref "TFT") (pin "8") (pinfunction "8_8") (pintype "passive"))
    )
    (net (code "126") (name "unconnected-(TFT-Pad10)") (class "Default")
      (node (ref "TFT") (pin "10") (pinfunction "10_10") (pintype "passive"))
    )
    (net (code "127") (name "unconnected-(TFT-Pad12)") (class "Default")
      (node (ref "TFT") (pin "12") (pinfunction "12_12") (pintype "passive"))
    )
    (net (code "128") (name "unconnected-(TFT-Pad14)") (class "Default")
      (node (ref "TFT") (pin "14") (pinfunction "14_14") (pintype "passive"))
    )
    (net (code "129") (name "unconnected-(TFT-Pad16)") (class "Default")
      (node (ref "TFT") (pin "16") (pinfunction "16_16") (pintype "passive"))
    )
    (net (code "130") (name "unconnected-(TFT-Pad24)") (class "Default")
      (node (ref "TFT") (pin "24") (pinfunction "24_24") (pintype "passive"))
    )
    (net (code "131") (name "unconnected-(TFT-Pad31)") (class "Default")
      (node (ref "TFT") (pin "31") (pinfunction "31_31") (pintype "passive"))
    )
    (net (code "132") (name "unconnected-(TFT-Pad35)") (class "Default")
      (node (ref "TFT") (pin "35") (pinfunction "35_35") (pintype "passive"))
    )
    (net (code "133") (name "unconnected-(TFT-Pad38)") (class "Default")
      (node (ref "TFT") (pin "38") (pinfunction "38_38") (pintype "passive"))
    )
    (net (code "134") (name "unconnected-(TFT-Pad39)") (class "Default")
      (node (ref "TFT") (pin "39") (pinfunction "39_39") (pintype "passive"))
    )
    (net (code "135") (name "unconnected-(TFT-Pad40)") (class "Default")
      (node (ref "TFT") (pin "40") (pinfunction "40_40") (pintype "passive"))
    )
  )
)
